# LED_Array.net
KiCad netlist of a schematic drawn in Altium Designer
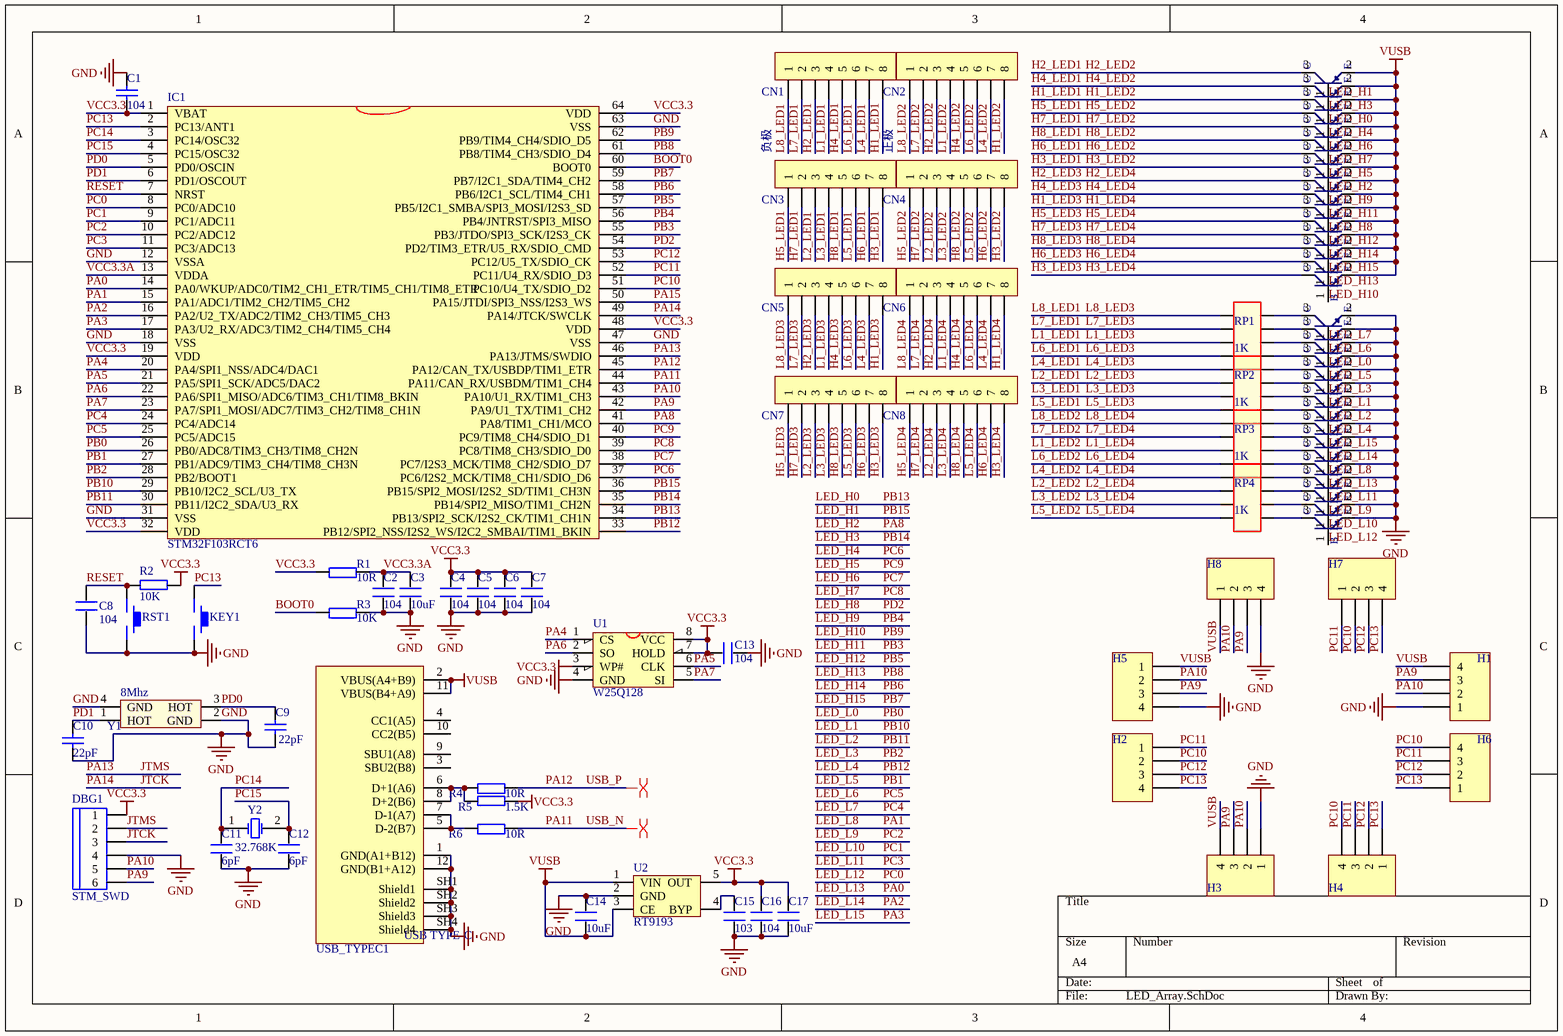
[diagram p0: LED_Array.SchDoc]

(export (version "E")
  (design (tool "Eeschema 10.0.6"))
  (components
    (comp (ref "C1") (value "104") (footprint "C 0603_L") (libsource (lib "L476") (part "CAP")))
    (comp (ref "C2")
      (value "104")
      (footprint "C 0603_L")
      (libsource (lib "WarShip V3 STM32103封装库") (part "C"))
    )
    (comp (ref "C3")
      (value "10uF")
      (footprint "C 0603_L")
      (libsource (lib "WarShip V3 STM32103封装库") (part "C"))
    )
    (comp (ref "C4")
      (value "104")
      (footprint "C 0603_L")
      (libsource (lib "WarShip V3 STM32103封装库") (part "C"))
    )
    (comp (ref "C5")
      (value "104")
      (footprint "C 0603_L")
      (libsource (lib "WarShip V3 STM32103封装库") (part "C"))
    )
    (comp (ref "C6")
      (value "104")
      (footprint "C 0603_L")
      (libsource (lib "WarShip V3 STM32103封装库") (part "C"))
    )
    (comp (ref "C7")
      (value "104")
      (footprint "C 0603_L")
      (libsource (lib "WarShip V3 STM32103封装库") (part "C"))
    )
    (comp (ref "C8")
      (value "104")
      (footprint "C 0603_L")
      (libsource (lib "WarShip V3 STM32103封装库") (part "C"))
    )
    (comp (ref "C9") (value "22pF") (footprint "C 0603_L") (libsource (lib "L476") (part "CAP")))
    (comp (ref "C10") (value "22pF") (footprint "C 0603_L") (libsource (lib "L476") (part "CAP")))
    (comp (ref "C11")
      (value "6pF")
      (footprint "C 0603_L")
      (libsource (lib "WarShip V3 STM32103封装库") (part "C"))
    )
    (comp (ref "C12")
      (value "6pF")
      (footprint "C 0603_L")
      (libsource (lib "WarShip V3 STM32103封装库") (part "C"))
    )
    (comp (ref "C13")
      (value "104")
      (footprint "C 0603_L")
      (libsource (lib "WarShip V3 STM32103封装库") (part "C"))
    )
    (comp (ref "C14")
      (value "10uF")
      (footprint "C 0603_L")
      (libsource (lib "WarShip V3 STM32103封装库") (part "C"))
    )
    (comp (ref "C15")
      (value "103")
      (footprint "C 0603_L")
      (libsource (lib "WarShip V3 STM32103封装库") (part "C"))
    )
    (comp (ref "C16")
      (value "104")
      (footprint "C 0603_L")
      (libsource (lib "WarShip V3 STM32103封装库") (part "C"))
    )
    (comp (ref "C17")
      (value "10uF")
      (footprint "C 0603_L")
      (libsource (lib "WarShip V3 STM32103封装库") (part "C"))
    )
    (comp (ref "CN1")
      (value "HDR-1X8")
      (footprint "HDR2.54-Y-LI-8P")
      (description "8P接插件")
      (libsource (lib "LovelessingSch") (part "Header 8"))
    )
    (comp (ref "CN2")
      (value "HDR-1X8")
      (footprint "HDR2.54-Y-LI-8P")
      (description "8P接插件")
      (libsource (lib "LovelessingSch") (part "Header 8"))
    )
    (comp (ref "CN3")
      (value "HDR-1X8")
      (footprint "HDR2.54-Y-LI-8P")
      (description "8P接插件")
      (libsource (lib "LovelessingSch") (part "Header 8"))
    )
    (comp (ref "CN4")
      (value "HDR-1X8")
      (footprint "HDR2.54-Y-LI-8P")
      (description "8P接插件")
      (libsource (lib "LovelessingSch") (part "Header 8"))
    )
    (comp (ref "CN5")
      (value "HDR-1X8")
      (footprint "HDR2.54-Y-LI-8P")
      (description "8P接插件")
      (libsource (lib "LovelessingSch") (part "Header 8"))
    )
    (comp (ref "CN6")
      (value "HDR-1X8")
      (footprint "HDR2.54-Y-LI-8P")
      (description "8P接插件")
      (libsource (lib "LovelessingSch") (part "Header 8"))
    )
    (comp (ref "CN7")
      (value "HDR-1X8")
      (footprint "HDR2.54-Y-LI-8P")
      (description "8P接插件")
      (libsource (lib "LovelessingSch") (part "Header 8"))
    )
    (comp (ref "CN8")
      (value "HDR-1X8")
      (footprint "HDR2.54-Y-LI-8P")
      (description "8P接插件")
      (libsource (lib "LovelessingSch") (part "Header 8"))
    )
    (comp (ref "DBG1")
      (value "STM_SWD")
      (footprint "SH1.0 S-W-6P")
      (libsource (lib "MiniFly ") (part "HEAD6"))
    )
    (comp (ref "H1")
      (value "Header 4")
      (footprint "HDR2.54-WI-4P")
      (description "Header, 4-Pin")
      (fields (field (name "PUBLISHER") "Altium Limited"))
      (libsource (lib "") (part "Header 4_1"))
    )
    (comp (ref "H2")
      (value "Header 4")
      (footprint "HDR2.54-WI-4P")
      (description "Header, 4-Pin")
      (fields (field (name "PUBLISHER") "Altium Limited"))
      (libsource (lib "LovelessingSch") (part "Header 4"))
    )
    (comp (ref "H3")
      (value "Header 4")
      (footprint "HDR2.54-WI-4P")
      (description "Header, 4-Pin")
      (fields (field (name "PUBLISHER") "Altium Limited"))
      (libsource (lib "LovelessingSch") (part "Header 4"))
    )
    (comp (ref "H4")
      (value "Header 4")
      (footprint "HDR2.54-WI-4P")
      (description "Header, 4-Pin")
      (fields (field (name "PUBLISHER") "Altium Limited"))
      (libsource (lib "LovelessingSch") (part "Header 4"))
    )
    (comp (ref "H5")
      (value "Header 4")
      (footprint "HDR2.54-WI-4P")
      (description "Header, 4-Pin")
      (fields (field (name "PUBLISHER") "Altium Limited"))
      (libsource (lib "LovelessingSch") (part "Header 4"))
    )
    (comp (ref "H6")
      (value "Header 4")
      (footprint "HDR2.54-WI-4P")
      (description "Header, 4-Pin")
      (fields (field (name "PUBLISHER") "Altium Limited"))
      (libsource (lib "") (part "Header 4_1"))
    )
    (comp (ref "H7")
      (value "Header 4")
      (footprint "HDR2.54-WI-4P")
      (description "Header, 4-Pin")
      (fields (field (name "PUBLISHER") "Altium Limited"))
      (libsource (lib "") (part "Header 4_1"))
    )
    (comp (ref "H8")
      (value "Header 4")
      (footprint "HDR2.54-WI-4P")
      (description "Header, 4-Pin")
      (fields (field (name "PUBLISHER") "Altium Limited"))
      (libsource (lib "") (part "Header 4_1"))
    )
    (comp (ref "IC1")
      (value "STM32F103RCT6")
      (footprint "LQFP64 10X10_L")
      (libsource (lib "MiniSTM32 V3.0封装库") (part "STM32F103RDT6"))
    )
    (comp (ref "KEY1")
      (value "KEY-SMD")
      (footprint "TSW SMD-3*6*2.5")
      (description "KEY,SMD,324225")
      (libsource (lib "Pandora_STM32L4_Board_V2.4") (part "S-KEY-SMD-324225"))
    )
    (comp (ref "Q1")
      (value "8550")
      (footprint "SOT23-3L")
      (libsource (lib "LovelessingSch") (part "8550PNP"))
    )
    (comp (ref "Q2")
      (value "8550")
      (footprint "SOT23-3L")
      (libsource (lib "LovelessingSch") (part "8550PNP"))
    )
    (comp (ref "Q3")
      (value "8550")
      (footprint "SOT23-3L")
      (libsource (lib "LovelessingSch") (part "8550PNP"))
    )
    (comp (ref "Q4")
      (value "8550")
      (footprint "SOT23-3L")
      (libsource (lib "LovelessingSch") (part "8550PNP"))
    )
    (comp (ref "Q5")
      (value "8550")
      (footprint "SOT23-3L")
      (libsource (lib "LovelessingSch") (part "8550PNP"))
    )
    (comp (ref "Q6")
      (value "8550")
      (footprint "SOT23-3L")
      (libsource (lib "LovelessingSch") (part "8550PNP"))
    )
    (comp (ref "Q7")
      (value "8550")
      (footprint "SOT23-3L")
      (libsource (lib "LovelessingSch") (part "8550PNP"))
    )
    (comp (ref "Q8")
      (value "8550")
      (footprint "SOT23-3L")
      (libsource (lib "LovelessingSch") (part "8550PNP"))
    )
    (comp (ref "Q9")
      (value "8550")
      (footprint "SOT23-3L")
      (libsource (lib "LovelessingSch") (part "8550PNP"))
    )
    (comp (ref "Q10")
      (value "8550")
      (footprint "SOT23-3L")
      (libsource (lib "LovelessingSch") (part "8550PNP"))
    )
    (comp (ref "Q11")
      (value "8550")
      (footprint "SOT23-3L")
      (libsource (lib "LovelessingSch") (part "8550PNP"))
    )
    (comp (ref "Q12")
      (value "8550")
      (footprint "SOT23-3L")
      (libsource (lib "LovelessingSch") (part "8550PNP"))
    )
    (comp (ref "Q13")
      (value "8550")
      (footprint "SOT23-3L")
      (libsource (lib "LovelessingSch") (part "8550PNP"))
    )
    (comp (ref "Q14")
      (value "8550")
      (footprint "SOT23-3L")
      (libsource (lib "LovelessingSch") (part "8550PNP"))
    )
    (comp (ref "Q15")
      (value "8550")
      (footprint "SOT23-3L")
      (libsource (lib "LovelessingSch") (part "8550PNP"))
    )
    (comp (ref "Q16")
      (value "8550")
      (footprint "SOT23-3L")
      (libsource (lib "LovelessingSch") (part "8550PNP"))
    )
    (comp (ref "Q17")
      (value "8050")
      (footprint "SOT23-3L")
      (libsource (lib "LovelessingSch") (part "8050NPN"))
    )
    (comp (ref "Q18")
      (value "8050")
      (footprint "SOT23-3L")
      (libsource (lib "LovelessingSch") (part "8050NPN"))
    )
    (comp (ref "Q19")
      (value "8050")
      (footprint "SOT23-3L")
      (libsource (lib "LovelessingSch") (part "8050NPN"))
    )
    (comp (ref "Q20")
      (value "8050")
      (footprint "SOT23-3L")
      (libsource (lib "LovelessingSch") (part "8050NPN"))
    )
    (comp (ref "Q21")
      (value "8050")
      (footprint "SOT23-3L")
      (libsource (lib "LovelessingSch") (part "8050NPN"))
    )
    (comp (ref "Q22")
      (value "8050")
      (footprint "SOT23-3L")
      (libsource (lib "LovelessingSch") (part "8050NPN"))
    )
    (comp (ref "Q23")
      (value "8050")
      (footprint "SOT23-3L")
      (libsource (lib "LovelessingSch") (part "8050NPN"))
    )
    (comp (ref "Q24")
      (value "8050")
      (footprint "SOT23-3L")
      (libsource (lib "LovelessingSch") (part "8050NPN"))
    )
    (comp (ref "Q25")
      (value "8050")
      (footprint "SOT23-3L")
      (libsource (lib "LovelessingSch") (part "8050NPN"))
    )
    (comp (ref "Q26")
      (value "8050")
      (footprint "SOT23-3L")
      (libsource (lib "LovelessingSch") (part "8050NPN"))
    )
    (comp (ref "Q27")
      (value "8050")
      (footprint "SOT23-3L")
      (libsource (lib "LovelessingSch") (part "8050NPN"))
    )
    (comp (ref "Q28")
      (value "8050")
      (footprint "SOT23-3L")
      (libsource (lib "LovelessingSch") (part "8050NPN"))
    )
    (comp (ref "Q29")
      (value "8050")
      (footprint "SOT23-3L")
      (libsource (lib "LovelessingSch") (part "8050NPN"))
    )
    (comp (ref "Q30")
      (value "8050")
      (footprint "SOT23-3L")
      (libsource (lib "LovelessingSch") (part "8050NPN"))
    )
    (comp (ref "Q31")
      (value "8050")
      (footprint "SOT23-3L")
      (libsource (lib "LovelessingSch") (part "8050NPN"))
    )
    (comp (ref "Q32")
      (value "8050")
      (footprint "SOT23-3L")
      (libsource (lib "LovelessingSch") (part "8050NPN"))
    )
    (comp (ref "R1")
      (value "10R")
      (footprint "R 0603_L")
      (libsource (lib "WarShip V3 STM32103封装库") (part "R"))
    )
    (comp (ref "R2")
      (value "10K")
      (footprint "R 0603_L")
      (libsource (lib "WarShip V3 STM32103封装库") (part "R"))
    )
    (comp (ref "R3")
      (value "10K")
      (footprint "R 0603_L")
      (libsource (lib "WarShip V3 STM32103封装库") (part "R"))
    )
    (comp (ref "R4")
      (value "10R")
      (footprint "R 0603_L")
      (libsource (lib "WarShip V3 STM32103封装库") (part "R"))
    )
    (comp (ref "R5")
      (value "1.5K")
      (footprint "R 0603_L")
      (libsource (lib "WarShip V3 STM32103封装库") (part "R"))
    )
    (comp (ref "R6")
      (value "10R")
      (footprint "R 0603_L")
      (libsource (lib "WarShip V3 STM32103封装库") (part "R"))
    )
    (comp (ref "RP1")
      (value "1K")
      (footprint "P_pack")
      (description "贴片排阻")
      (libsource (lib "LovelessingSch") (part "R_pack"))
    )
    (comp (ref "RP2")
      (value "1K")
      (footprint "P_pack")
      (description "贴片排阻")
      (libsource (lib "LovelessingSch") (part "R_pack"))
    )
    (comp (ref "RP3")
      (value "1K")
      (footprint "P_pack")
      (description "贴片排阻")
      (libsource (lib "LovelessingSch") (part "R_pack"))
    )
    (comp (ref "RP4")
      (value "1K")
      (footprint "P_pack")
      (description "贴片排阻")
      (libsource (lib "LovelessingSch") (part "R_pack"))
    )
    (comp (ref "RST1")
      (value "KEY-SMD")
      (footprint "TSW SMD-3*6*2.5")
      (description "KEY,SMD,324225")
      (libsource (lib "Pandora_STM32L4_Board_V2.4") (part "S-KEY-SMD-324225"))
    )
    (comp (ref "U1")
      (value "W25Q128")
      (footprint "SOP8W_L")
      (description "W25X16;SST25VF016;MX25L1605")
      (libsource (lib "WarShip V3 STM32103封装库") (part "W25X16"))
    )
    (comp (ref "U2")
      (value "RT9193")
      (footprint "SOT23-5L")
      (description "3.3V 500mA LDO")
      (libsource (lib "STM32H743核心板封装库") (part "CAT6219-330TD"))
    )
    (comp (ref "USB_TYPEC1")
      (value "USB TypeC")
      (footprint "USB Type-C")
      (description "12P TypeC 母座")
      (libsource (lib "ESP32_Weather") (part "USB Type-C"))
    )
    (comp (ref "Y1")
      (value "8Mhz")
      (footprint "XTAL-3225-4P")
      (description "3225贴片无源晶振")
      (libsource (lib "ALIENTEK_COMPONENT") (part "XTAL_3225"))
    )
    (comp (ref "Y2")
      (value "32.768K")
      (footprint "OSC 3215-2P")
      (description "Crystal Oscillator")
      (fields (field (name "PUBLISHER") "Altium Limited"))
      (libsource (lib "WarShip V3 STM32103封装库") (part "XTAL"))
    )
  )
  (nets
    (net (code "1") (name "/BOOT0") (class "Default")
      (node (ref "IC1") (pin "60") (pinfunction "BOOT0_60") (pintype "passive"))
      (node (ref "R3") (pin "1") (pintype "passive"))
    )
    (net (code "2") (name "/H1_LED1") (class "Default")
      (node (ref "CN1") (pin "8") (pinfunction "8_8") (pintype "passive"))
      (node (ref "CN2") (pin "8") (pinfunction "8_8") (pintype "passive"))
      (node (ref "Q3") (pin "3") (pinfunction "C_3") (pintype "passive"))
    )
    (net (code "3") (name "/H1_LED3") (class "Default")
      (node (ref "CN5") (pin "8") (pinfunction "8_8") (pintype "passive"))
      (node (ref "CN6") (pin "8") (pinfunction "8_8") (pintype "passive"))
      (node (ref "Q11") (pin "3") (pinfunction "C_3") (pintype "passive"))
    )
    (net (code "4") (name "/H2_LED1") (class "Default")
      (node (ref "CN1") (pin "3") (pinfunction "3_3") (pintype "passive"))
      (node (ref "CN2") (pin "3") (pinfunction "3_3") (pintype "passive"))
      (node (ref "Q1") (pin "3") (pinfunction "C_3") (pintype "passive"))
    )
    (net (code "5") (name "/H2_LED3") (class "Default")
      (node (ref "CN5") (pin "3") (pinfunction "3_3") (pintype "passive"))
      (node (ref "CN6") (pin "3") (pinfunction "3_3") (pintype "passive"))
      (node (ref "Q9") (pin "3") (pinfunction "C_3") (pintype "passive"))
    )
    (net (code "6") (name "/H3_LED1") (class "Default")
      (node (ref "CN3") (pin "8") (pinfunction "8_8") (pintype "passive"))
      (node (ref "CN4") (pin "8") (pinfunction "8_8") (pintype "passive"))
      (node (ref "Q8") (pin "3") (pinfunction "C_3") (pintype "passive"))
    )
    (net (code "7") (name "/H3_LED3") (class "Default")
      (node (ref "CN7") (pin "8") (pinfunction "8_8") (pintype "passive"))
      (node (ref "CN8") (pin "8") (pinfunction "8_8") (pintype "passive"))
      (node (ref "Q16") (pin "3") (pinfunction "C_3") (pintype "passive"))
    )
    (net (code "8") (name "/H4_LED1") (class "Default")
      (node (ref "CN1") (pin "5") (pinfunction "5_5") (pintype "passive"))
      (node (ref "CN2") (pin "5") (pinfunction "5_5") (pintype "passive"))
      (node (ref "Q2") (pin "3") (pinfunction "C_3") (pintype "passive"))
    )
    (net (code "9") (name "/H4_LED3") (class "Default")
      (node (ref "CN5") (pin "5") (pinfunction "5_5") (pintype "passive"))
      (node (ref "CN6") (pin "5") (pinfunction "5_5") (pintype "passive"))
      (node (ref "Q10") (pin "3") (pinfunction "C_3") (pintype "passive"))
    )
    (net (code "10") (name "/H5_LED1") (class "Default")
      (node (ref "CN3") (pin "1") (pinfunction "1_1") (pintype "passive"))
      (node (ref "CN4") (pin "1") (pinfunction "1_1") (pintype "passive"))
      (node (ref "Q4") (pin "3") (pinfunction "C_3") (pintype "passive"))
    )
    (net (code "11") (name "/H5_LED3") (class "Default")
      (node (ref "CN7") (pin "1") (pinfunction "1_1") (pintype "passive"))
      (node (ref "CN8") (pin "1") (pinfunction "1_1") (pintype "passive"))
      (node (ref "Q12") (pin "3") (pinfunction "C_3") (pintype "passive"))
    )
    (net (code "12") (name "/H6_LED1") (class "Default")
      (node (ref "CN3") (pin "7") (pinfunction "7_7") (pintype "passive"))
      (node (ref "CN4") (pin "7") (pinfunction "7_7") (pintype "passive"))
      (node (ref "Q7") (pin "3") (pinfunction "C_3") (pintype "passive"))
    )
    (net (code "13") (name "/H6_LED3") (class "Default")
      (node (ref "CN7") (pin "7") (pinfunction "7_7") (pintype "passive"))
      (node (ref "CN8") (pin "7") (pinfunction "7_7") (pintype "passive"))
      (node (ref "Q15") (pin "3") (pinfunction "C_3") (pintype "passive"))
    )
    (net (code "14") (name "/H7_LED1") (class "Default")
      (node (ref "CN3") (pin "2") (pinfunction "2_2") (pintype "passive"))
      (node (ref "CN4") (pin "2") (pinfunction "2_2") (pintype "passive"))
      (node (ref "Q5") (pin "3") (pinfunction "C_3") (pintype "passive"))
    )
    (net (code "15") (name "/H7_LED3") (class "Default")
      (node (ref "CN7") (pin "2") (pinfunction "2_2") (pintype "passive"))
      (node (ref "CN8") (pin "2") (pinfunction "2_2") (pintype "passive"))
      (node (ref "Q13") (pin "3") (pinfunction "C_3") (pintype "passive"))
    )
    (net (code "16") (name "/H8_LED1") (class "Default")
      (node (ref "CN3") (pin "5") (pinfunction "5_5") (pintype "passive"))
      (node (ref "CN4") (pin "5") (pinfunction "5_5") (pintype "passive"))
      (node (ref "Q6") (pin "3") (pinfunction "C_3") (pintype "passive"))
    )
    (net (code "17") (name "/H8_LED3") (class "Default")
      (node (ref "CN7") (pin "5") (pinfunction "5_5") (pintype "passive"))
      (node (ref "CN8") (pin "5") (pinfunction "5_5") (pintype "passive"))
      (node (ref "Q14") (pin "3") (pinfunction "C_3") (pintype "passive"))
    )
    (net (code "18") (name "/JTCK") (class "Default")
      (node (ref "DBG1") (pin "3") (pinfunction "3_3") (pintype "passive"))
      (node (ref "IC1") (pin "49") (pinfunction "PA14/JTCK/SWCLK_49") (pintype "passive"))
    )
    (net (code "19") (name "/JTMS") (class "Default")
      (node (ref "DBG1") (pin "2") (pinfunction "2_2") (pintype "passive"))
      (node (ref "IC1") (pin "46") (pinfunction "PA13/JTMS/SWDIO_46") (pintype "passive"))
    )
    (net (code "20") (name "/L1_LED1") (class "Default")
      (node (ref "CN1") (pin "4") (pinfunction "4_4") (pintype "passive"))
      (node (ref "CN5") (pin "4") (pinfunction "4_4") (pintype "passive"))
      (node (ref "RP1") (pin "5") (pintype "passive"))
    )
    (net (code "21") (name "/L1_LED2") (class "Default")
      (node (ref "CN2") (pin "4") (pinfunction "4_4") (pintype "passive"))
      (node (ref "CN6") (pin "4") (pinfunction "4_4") (pintype "passive"))
      (node (ref "RP3") (pin "5") (pintype "passive"))
    )
    (net (code "22") (name "/L2_LED1") (class "Default")
      (node (ref "CN3") (pin "3") (pinfunction "3_3") (pintype "passive"))
      (node (ref "CN7") (pin "3") (pinfunction "3_3") (pintype "passive"))
      (node (ref "RP2") (pin "3") (pintype "passive"))
    )
    (net (code "23") (name "/L2_LED2") (class "Default")
      (node (ref "CN4") (pin "3") (pinfunction "3_3") (pintype "passive"))
      (node (ref "CN8") (pin "3") (pinfunction "3_3") (pintype "passive"))
      (node (ref "RP4") (pin "3") (pintype "passive"))
    )
    (net (code "24") (name "/L3_LED1") (class "Default")
      (node (ref "CN3") (pin "4") (pinfunction "4_4") (pintype "passive"))
      (node (ref "CN7") (pin "4") (pinfunction "4_4") (pintype "passive"))
      (node (ref "RP2") (pin "5") (pintype "passive"))
    )
    (net (code "25") (name "/L3_LED2") (class "Default")
      (node (ref "CN4") (pin "4") (pinfunction "4_4") (pintype "passive"))
      (node (ref "CN8") (pin "4") (pinfunction "4_4") (pintype "passive"))
      (node (ref "RP4") (pin "5") (pintype "passive"))
    )
    (net (code "26") (name "/L4_LED1") (class "Default")
      (node (ref "CN1") (pin "7") (pinfunction "7_7") (pintype "passive"))
      (node (ref "CN5") (pin "7") (pinfunction "7_7") (pintype "passive"))
      (node (ref "RP2") (pin "1") (pinfunction "1_1") (pintype "passive"))
    )
    (net (code "27") (name "/L4_LED2") (class "Default")
      (node (ref "CN2") (pin "7") (pinfunction "7_7") (pintype "passive"))
      (node (ref "CN6") (pin "7") (pinfunction "7_7") (pintype "passive"))
      (node (ref "RP4") (pin "1") (pinfunction "1_1") (pintype "passive"))
    )
    (net (code "28") (name "/L5_LED1") (class "Default")
      (node (ref "CN3") (pin "6") (pinfunction "6_6") (pintype "passive"))
      (node (ref "CN7") (pin "6") (pinfunction "6_6") (pintype "passive"))
      (node (ref "RP2") (pin "7") (pintype "passive"))
    )
    (net (code "29") (name "/L5_LED2") (class "Default")
      (node (ref "CN4") (pin "6") (pinfunction "6_6") (pintype "passive"))
      (node (ref "CN8") (pin "6") (pinfunction "6_6") (pintype "passive"))
      (node (ref "RP4") (pin "7") (pintype "passive"))
    )
    (net (code "30") (name "/L6_LED1") (class "Default")
      (node (ref "CN1") (pin "6") (pinfunction "6_6") (pintype "passive"))
      (node (ref "CN5") (pin "6") (pinfunction "6_6") (pintype "passive"))
      (node (ref "RP1") (pin "7") (pintype "passive"))
    )
    (net (code "31") (name "/L6_LED2") (class "Default")
      (node (ref "CN2") (pin "6") (pinfunction "6_6") (pintype "passive"))
      (node (ref "CN6") (pin "6") (pinfunction "6_6") (pintype "passive"))
      (node (ref "RP3") (pin "7") (pintype "passive"))
    )
    (net (code "32") (name "/L7_LED1") (class "Default")
      (node (ref "CN1") (pin "2") (pinfunction "2_2") (pintype "passive"))
      (node (ref "CN5") (pin "2") (pinfunction "2_2") (pintype "passive"))
      (node (ref "RP1") (pin "3") (pintype "passive"))
    )
    (net (code "33") (name "/L7_LED2") (class "Default")
      (node (ref "CN2") (pin "2") (pinfunction "2_2") (pintype "passive"))
      (node (ref "CN6") (pin "2") (pinfunction "2_2") (pintype "passive"))
      (node (ref "RP3") (pin "3") (pintype "passive"))
    )
    (net (code "34") (name "/L8_LED1") (class "Default")
      (node (ref "CN1") (pin "1") (pinfunction "1_1") (pintype "passive"))
      (node (ref "CN5") (pin "1") (pinfunction "1_1") (pintype "passive"))
      (node (ref "RP1") (pin "1") (pinfunction "1_1") (pintype "passive"))
    )
    (net (code "35") (name "/L8_LED2") (class "Default")
      (node (ref "CN2") (pin "1") (pinfunction "1_1") (pintype "passive"))
      (node (ref "CN6") (pin "1") (pinfunction "1_1") (pintype "passive"))
      (node (ref "RP3") (pin "1") (pinfunction "1_1") (pintype "passive"))
    )
    (net (code "36") (name "/LED_H0") (class "Default")
      (node (ref "IC1") (pin "34") (pinfunction "PB13/SPI2_SCK/I2S2_CK/TIM1_CH1N_34") (pintype "passive"))
      (node (ref "Q3") (pin "1") (pinfunction "B_1") (pintype "passive"))
    )
    (net (code "37") (name "/LED_H1") (class "Default")
      (node (ref "IC1") (pin "36") (pinfunction "PB15/SPI2_MOSI/I2S2_SD/TIM1_CH3N_36") (pintype "passive"))
      (node (ref "Q1") (pin "1") (pinfunction "B_1") (pintype "passive"))
    )
    (net (code "38") (name "/LED_H2") (class "Default")
      (node (ref "IC1") (pin "41") (pinfunction "PA8/TIM1_CH1/MCO_41") (pintype "passive"))
      (node (ref "Q8") (pin "1") (pinfunction "B_1") (pintype "passive"))
    )
    (net (code "39") (name "/LED_H3") (class "Default")
      (node (ref "IC1") (pin "35") (pinfunction "PB14/SPI2_MISO/TIM1_CH2N_35") (pintype "passive"))
      (node (ref "Q2") (pin "1") (pinfunction "B_1") (pintype "passive"))
    )
    (net (code "40") (name "/LED_H4") (class "Default")
      (node (ref "IC1") (pin "37") (pinfunction "PC6/I2S2_MCK/TIM8_CH1/SDIO_D6_37") (pintype "passive"))
      (node (ref "Q4") (pin "1") (pinfunction "B_1") (pintype "passive"))
    )
    (net (code "41") (name "/LED_H5") (class "Default")
      (node (ref "IC1") (pin "40") (pinfunction "PC9/TIM8_CH4/SDIO_D1_40") (pintype "passive"))
      (node (ref "Q7") (pin "1") (pinfunction "B_1") (pintype "passive"))
    )
    (net (code "42") (name "/LED_H6") (class "Default")
      (node (ref "IC1") (pin "38") (pinfunction "PC7/I2S3_MCK/TIM8_CH2/SDIO_D7_38") (pintype "passive"))
      (node (ref "Q5") (pin "1") (pinfunction "B_1") (pintype "passive"))
    )
    (net (code "43") (name "/LED_H7") (class "Default")
      (node (ref "IC1") (pin "39") (pinfunction "PC8/TIM8_CH3/SDIO_D0_39") (pintype "passive"))
      (node (ref "Q6") (pin "1") (pinfunction "B_1") (pintype "passive"))
    )
    (net (code "44") (name "/LED_H8") (class "Default")
      (node (ref "IC1") (pin "54") (pinfunction "PD2/TIM3_ETR/U5_RX/SDIO_CMD_54") (pintype "passive"))
      (node (ref "Q11") (pin "1") (pinfunction "B_1") (pintype "passive"))
    )
    (net (code "45") (name "/LED_H9") (class "Default")
      (node (ref "IC1") (pin "56") (pinfunction "PB4/JNTRST/SPI3_MISO_56") (pintype "passive"))
      (node (ref "Q9") (pin "1") (pinfunction "B_1") (pintype "passive"))
    )
    (net (code "46") (name "/LED_H10") (class "Default")
      (node (ref "IC1") (pin "62") (pinfunction "PB9/TIM4_CH4/SDIO_D5_62") (pintype "passive"))
      (node (ref "Q16") (pin "1") (pinfunction "B_1") (pintype "passive"))
    )
    (net (code "47") (name "/LED_H11") (class "Default")
      (node (ref "IC1") (pin "55") (pinfunction "PB3/JTDO/SPI3_SCK/I2S3_CK_55") (pintype "passive"))
      (node (ref "Q10") (pin "1") (pinfunction "B_1") (pintype "passive"))
    )
    (net (code "48") (name "/LED_H12") (class "Default")
      (node (ref "IC1") (pin "57") (pinfunction "PB5/I2C1_SMBA/SPI3_MOSI/I2S3_SD_57") (pintype "passive"))
      (node (ref "Q12") (pin "1") (pinfunction "B_1") (pintype "passive"))
    )
    (net (code "49") (name "/LED_H13") (class "Default")
      (node (ref "IC1") (pin "61") (pinfunction "PB8/TIM4_CH3/SDIO_D4_61") (pintype "passive"))
      (node (ref "Q15") (pin "1") (pinfunction "B_1") (pintype "passive"))
    )
    (net (code "50") (name "/LED_H14") (class "Default")
      (node (ref "IC1") (pin "58") (pinfunction "PB6/I2C1_SCL/TIM4_CH1_58") (pintype "passive"))
      (node (ref "Q13") (pin "1") (pinfunction "B_1") (pintype "passive"))
    )
    (net (code "51") (name "/LED_H15") (class "Default")
      (node (ref "IC1") (pin "59") (pinfunction "PB7/I2C1_SDA/TIM4_CH2_59") (pintype "passive"))
      (node (ref "Q14") (pin "1") (pinfunction "B_1") (pintype "passive"))
    )
    (net (code "52") (name "/LED_L0") (class "Default")
      (node (ref "IC1") (pin "26") (pinfunction "PB0/ADC8/TIM3_CH3/TIM8_CH2N_26") (pintype "passive"))
      (node (ref "Q19") (pin "1") (pinfunction "B_1") (pintype "passive"))
    )
    (net (code "53") (name "/LED_L1") (class "Default")
      (node (ref "IC1") (pin "29") (pinfunction "PB10/I2C2_SCL/U3_TX_29") (pintype "passive"))
      (node (ref "Q22") (pin "1") (pinfunction "B_1") (pintype "passive"))
    )
    (net (code "54") (name "/LED_L2") (class "Default")
      (node (ref "IC1") (pin "30") (pinfunction "PB11/I2C2_SDA/U3_RX_30") (pintype "passive"))
      (node (ref "Q23") (pin "1") (pinfunction "B_1") (pintype "passive"))
    )
    (net (code "55") (name "/LED_L3") (class "Default")
      (node (ref "IC1") (pin "28") (pinfunction "PB2/BOOT1_28") (pintype "passive"))
      (node (ref "Q21") (pin "1") (pinfunction "B_1") (pintype "passive"))
    )
    (net (code "56") (name "/LED_L4") (class "Default")
      (node (ref "IC1") (pin "33") (pinfunction "PB12/SPI2_NSS/I2S2_WS/I2C2_SMBAI/TIM1_BKIN_33") (pintype "passive"))
      (node (ref "Q24") (pin "1") (pinfunction "B_1") (pintype "passive"))
    )
    (net (code "57") (name "/LED_L5") (class "Default")
      (node (ref "IC1") (pin "27") (pinfunction "PB1/ADC9/TIM3_CH4/TIM8_CH3N_27") (pintype "passive"))
      (node (ref "Q20") (pin "1") (pinfunction "B_1") (pintype "passive"))
    )
    (net (code "58") (name "/LED_L6") (class "Default")
      (node (ref "IC1") (pin "25") (pinfunction "PC5/ADC15_25") (pintype "passive"))
      (node (ref "Q18") (pin "1") (pinfunction "B_1") (pintype "passive"))
    )
    (net (code "59") (name "/LED_L7") (class "Default")
      (node (ref "IC1") (pin "24") (pinfunction "PC4/ADC14_24") (pintype "passive"))
      (node (ref "Q17") (pin "1") (pinfunction "B_1") (pintype "passive"))
    )
    (net (code "60") (name "/LED_L8") (class "Default")
      (node (ref "IC1") (pin "15") (pinfunction "PA1/ADC1/TIM2_CH2/TIM5_CH2_15") (pintype "passive"))
      (node (ref "Q27") (pin "1") (pinfunction "B_1") (pintype "passive"))
    )
    (net (code "61") (name "/LED_L9") (class "Default")
      (node (ref "IC1") (pin "10") (pinfunction "PC2/ADC12_10") (pintype "passive"))
      (node (ref "Q30") (pin "1") (pinfunction "B_1") (pintype "passive"))
    )
    (net (code "62") (name "/LED_L10") (class "Default")
      (node (ref "IC1") (pin "9") (pinfunction "PC1/ADC11_9") (pintype "passive"))
      (node (ref "Q31") (pin "1") (pinfunction "B_1") (pintype "passive"))
    )
    (net (code "63") (name "/LED_L11") (class "Default")
      (node (ref "IC1") (pin "11") (pinfunction "PC3/ADC13_11") (pintype "passive"))
      (node (ref "Q29") (pin "1") (pinfunction "B_1") (pintype "passive"))
    )
    (net (code "64") (name "/LED_L12") (class "Default")
      (node (ref "IC1") (pin "8") (pinfunction "PC0/ADC10_8") (pintype "passive"))
      (node (ref "Q32") (pin "1") (pinfunction "B_1") (pintype "passive"))
    )
    (net (code "65") (name "/LED_L13") (class "Default")
      (node (ref "IC1") (pin "14") (pinfunction "PA0/WKUP/ADC0/TIM2_CH1_ETR/TIM5_CH1/TIM8_ETR_14") (pintype "passive"))
      (node (ref "Q28") (pin "1") (pinfunction "B_1") (pintype "passive"))
    )
    (net (code "66") (name "/LED_L14") (class "Default")
      (node (ref "IC1") (pin "16") (pinfunction "PA2/U2_TX/ADC2/TIM2_CH3/TIM5_CH3_16") (pintype "passive"))
      (node (ref "Q26") (pin "1") (pinfunction "B_1") (pintype "passive"))
    )
    (net (code "67") (name "/LED_L15") (class "Default")
      (node (ref "IC1") (pin "17") (pinfunction "PA3/U2_RX/ADC3/TIM2_CH4/TIM5_CH4_17") (pintype "passive"))
      (node (ref "Q25") (pin "1") (pinfunction "B_1") (pintype "passive"))
    )
    (net (code "68") (name "/PA4") (class "Default")
      (node (ref "IC1") (pin "20") (pinfunction "PA4/SPI1_NSS/ADC4/DAC1_20") (pintype "passive"))
      (node (ref "U1") (pin "1") (pinfunction "CS_1") (pintype "passive"))
    )
    (net (code "69") (name "/PA5") (class "Default")
      (node (ref "IC1") (pin "21") (pinfunction "PA5/SPI1_SCK/ADC5/DAC2_21") (pintype "passive"))
      (node (ref "U1") (pin "6") (pinfunction "CLK_6") (pintype "passive"))
    )
    (net (code "70") (name "/PA6") (class "Default")
      (node (ref "IC1") (pin "22") (pinfunction "PA6/SPI1_MISO/ADC6/TIM3_CH1/TIM8_BKIN_22") (pintype "passive"))
      (node (ref "U1") (pin "2") (pinfunction "SO_2") (pintype "passive"))
    )
    (net (code "71") (name "/PA7") (class "Default")
      (node (ref "IC1") (pin "23") (pinfunction "PA7/SPI1_MOSI/ADC7/TIM3_CH2/TIM8_CH1N_23") (pintype "passive"))
      (node (ref "U1") (pin "5") (pinfunction "SI_5") (pintype "passive"))
    )
    (net (code "72") (name "/PA9") (class "Default")
      (node (ref "DBG1") (pin "6") (pinfunction "6_6") (pintype "passive"))
      (node (ref "H1") (pin "3") (pinfunction "3_3") (pintype "passive"))
      (node (ref "H3") (pin "3") (pinfunction "3_3") (pintype "passive"))
      (node (ref "H5") (pin "3") (pinfunction "3_3") (pintype "passive"))
      (node (ref "H8") (pin "3") (pinfunction "3_3") (pintype "passive"))
      (node (ref "IC1") (pin "42") (pinfunction "PA9/U1_TX/TIM1_CH2_42") (pintype "passive"))
    )
    (net (code "73") (name "/PA10") (class "Default")
      (node (ref "DBG1") (pin "5") (pinfunction "5_5") (pintype "passive"))
      (node (ref "H1") (pin "2") (pinfunction "2_2") (pintype "passive"))
      (node (ref "H3") (pin "2") (pinfunction "2_2") (pintype "passive"))
      (node (ref "H5") (pin "2") (pinfunction "2_2") (pintype "passive"))
      (node (ref "H8") (pin "2") (pinfunction "2_2") (pintype "passive"))
      (node (ref "IC1") (pin "43") (pinfunction "PA10/U1_RX/TIM1_CH3_43") (pintype "passive"))
    )
    (net (code "74") (name "/PA11") (class "Default")
      (node (ref "IC1") (pin "44") (pinfunction "PA11/CAN_RX/USBDM/TIM1_CH4_44") (pintype "passive"))
      (node (ref "R6") (pin "2") (pintype "passive"))
    )
    (net (code "75") (name "/PA12") (class "Default")
      (node (ref "IC1") (pin "45") (pinfunction "PA12/CAN_TX/USBDP/TIM1_ETR_45") (pintype "passive"))
      (node (ref "R4") (pin "2") (pintype "passive"))
    )
    (net (code "76") (name "/PA15") (class "Default")
      (node (ref "IC1") (pin "50") (pinfunction "PA15/JTDI/SPI3_NSS/I2S3_WS_50") (pintype "passive"))
    )
    (net (code "77") (name "/PC10") (class "Default")
      (node (ref "H2") (pin "2") (pinfunction "2_2") (pintype "passive"))
      (node (ref "H4") (pin "4") (pinfunction "4_4") (pintype "passive"))
      (node (ref "H6") (pin "4") (pinfunction "4_4") (pintype "passive"))
      (node (ref "H7") (pin "2") (pinfunction "2_2") (pintype "passive"))
      (node (ref "IC1") (pin "51") (pinfunction "PC10/U4_TX/SDIO_D2_51") (pintype "passive"))
    )
    (net (code "78") (name "/PC11") (class "Default")
      (node (ref "H2") (pin "1") (pinfunction "1_1") (pintype "passive"))
      (node (ref "H4") (pin "3") (pinfunction "3_3") (pintype "passive"))
      (node (ref "H6") (pin "3") (pinfunction "3_3") (pintype "passive"))
      (node (ref "H7") (pin "1") (pinfunction "1_1") (pintype "passive"))
      (node (ref "IC1") (pin "52") (pinfunction "PC11/U4_RX/SDIO_D3_52") (pintype "passive"))
    )
    (net (code "79") (name "/PC12") (class "Default")
      (node (ref "H2") (pin "3") (pinfunction "3_3") (pintype "passive"))
      (node (ref "H4") (pin "2") (pinfunction "2_2") (pintype "passive"))
      (node (ref "H6") (pin "2") (pinfunction "2_2") (pintype "passive"))
      (node (ref "H7") (pin "3") (pinfunction "3_3") (pintype "passive"))
      (node (ref "IC1") (pin "53") (pinfunction "PC12/U5_TX/SDIO_CK_53") (pintype "passive"))
    )
    (net (code "80") (name "/PC13") (class "Default")
      (node (ref "H2") (pin "4") (pinfunction "4_4") (pintype "passive"))
      (node (ref "H4") (pin "1") (pinfunction "1_1") (pintype "passive"))
      (node (ref "H6") (pin "1") (pinfunction "1_1") (pintype "passive"))
      (node (ref "H7") (pin "4") (pinfunction "4_4") (pintype "passive"))
      (node (ref "IC1") (pin "2") (pinfunction "PC13/ANT1_2") (pintype "passive"))
      (node (ref "KEY1") (pin "1") (pinfunction "1_1") (pintype "passive"))
    )
    (net (code "81") (name "/PC14") (class "Default")
      (node (ref "C11") (pin "2") (pintype "passive"))
      (node (ref "IC1") (pin "3") (pinfunction "PC14/OSC32_3") (pintype "passive"))
      (node (ref "Y2") (pin "1") (pinfunction "OSC1_1") (pintype "passive"))
    )
    (net (code "82") (name "/PC15") (class "Default")
      (node (ref "C12") (pin "2") (pintype "passive"))
      (node (ref "IC1") (pin "4") (pinfunction "PC15/OSC32_4") (pintype "passive"))
      (node (ref "Y2") (pin "2") (pinfunction "OSC2_2") (pintype "passive"))
    )
    (net (code "83") (name "/PD0") (class "Default")
      (node (ref "C9") (pin "2") (pinfunction "2_2") (pintype "passive"))
      (node (ref "IC1") (pin "5") (pinfunction "PD0/OSCIN_5") (pintype "passive"))
      (node (ref "Y1") (pin "3") (pinfunction "HOT_3") (pintype "passive"))
    )
    (net (code "84") (name "/PD1") (class "Default")
      (node (ref "C10") (pin "2") (pinfunction "2_2") (pintype "passive"))
      (node (ref "IC1") (pin "6") (pinfunction "PD1/OSCOUT_6") (pintype "passive"))
      (node (ref "Y1") (pin "1") (pinfunction "HOT_1") (pintype "passive"))
    )
    (net (code "85") (name "/RESET") (class "Default")
      (node (ref "C8") (pin "2") (pintype "passive"))
      (node (ref "IC1") (pin "7") (pinfunction "NRST_7") (pintype "passive"))
      (node (ref "R2") (pin "2") (pintype "passive"))
      (node (ref "RST1") (pin "1") (pinfunction "1_1") (pintype "passive"))
    )
    (net (code "86") (name "/VCC3.3A") (class "Default")
      (node (ref "C2") (pin "2") (pintype "passive"))
      (node (ref "C3") (pin "2") (pintype "passive"))
      (node (ref "IC1") (pin "13") (pinfunction "VDDA_13") (pintype "passive"))
      (node (ref "R1") (pin "2") (pintype "passive"))
    )
    (net (code "87") (name "GND") (class "Default")
      (node (ref "C1") (pin "1") (pinfunction "1_1") (pintype "passive"))
      (node (ref "C10") (pin "1") (pinfunction "1_1") (pintype "passive"))
      (node (ref "C11") (pin "1") (pintype "passive"))
      (node (ref "C12") (pin "1") (pintype "passive"))
      (node (ref "C13") (pin "2") (pintype "passive"))
      (node (ref "C14") (pin "2") (pintype "passive"))
      (node (ref "C15") (pin "1") (pintype "passive"))
      (node (ref "C16") (pin "1") (pintype "passive"))
      (node (ref "C17") (pin "1") (pintype "passive"))
      (node (ref "C2") (pin "1") (pintype "passive"))
      (node (ref "C3") (pin "1") (pintype "passive"))
      (node (ref "C4") (pin "1") (pintype "passive"))
      (node (ref "C5") (pin "1") (pintype "passive"))
      (node (ref "C6") (pin "1") (pintype "passive"))
      (node (ref "C7") (pin "1") (pintype "passive"))
      (node (ref "C8") (pin "1") (pintype "passive"))
      (node (ref "C9") (pin "1") (pinfunction "1_1") (pintype "passive"))
      (node (ref "DBG1") (pin "4") (pinfunction "4_4") (pintype "passive"))
      (node (ref "H1") (pin "1") (pinfunction "1_1") (pintype "passive"))
      (node (ref "H3") (pin "1") (pinfunction "1_1") (pintype "passive"))
      (node (ref "H5") (pin "4") (pinfunction "4_4") (pintype "passive"))
      (node (ref "H8") (pin "4") (pinfunction "4_4") (pintype "passive"))
      (node (ref "IC1") (pin "12") (pinfunction "VSSA_12") (pintype "passive"))
      (node (ref "IC1") (pin "18") (pinfunction "VSS_18") (pintype "passive"))
      (node (ref "IC1") (pin "31") (pinfunction "VSS_31") (pintype "passive"))
      (node (ref "IC1") (pin "47") (pinfunction "VSS_47") (pintype "passive"))
      (node (ref "IC1") (pin "63") (pinfunction "VSS_63") (pintype "passive"))
      (node (ref "KEY1") (pin "2") (pinfunction "2_2") (pintype "passive"))
      (node (ref "Q17") (pin "2") (pinfunction "E_2") (pintype "passive"))
      (node (ref "Q18") (pin "2") (pinfunction "E_2") (pintype "passive"))
      (node (ref "Q19") (pin "2") (pinfunction "E_2") (pintype "passive"))
      (node (ref "Q20") (pin "2") (pinfunction "E_2") (pintype "passive"))
      (node (ref "Q21") (pin "2") (pinfunction "E_2") (pintype "passive"))
      (node (ref "Q22") (pin "2") (pinfunction "E_2") (pintype "passive"))
      (node (ref "Q23") (pin "2") (pinfunction "E_2") (pintype "passive"))
      (node (ref "Q24") (pin "2") (pinfunction "E_2") (pintype "passive"))
      (node (ref "Q25") (pin "2") (pinfunction "E_2") (pintype "passive"))
      (node (ref "Q26") (pin "2") (pinfunction "E_2") (pintype "passive"))
      (node (ref "Q27") (pin "2") (pinfunction "E_2") (pintype "passive"))
      (node (ref "Q28") (pin "2") (pinfunction "E_2") (pintype "passive"))
      (node (ref "Q29") (pin "2") (pinfunction "E_2") (pintype "passive"))
      (node (ref "Q30") (pin "2") (pinfunction "E_2") (pintype "passive"))
      (node (ref "Q31") (pin "2") (pinfunction "E_2") (pintype "passive"))
      (node (ref "Q32") (pin "2") (pinfunction "E_2") (pintype "passive"))
      (node (ref "R3") (pin "2") (pintype "passive"))
      (node (ref "RST1") (pin "2") (pinfunction "2_2") (pintype "passive"))
      (node (ref "U1") (pin "4") (pinfunction "GND_4") (pintype "passive"))
      (node (ref "U2") (pin "2") (pinfunction "GND_2") (pintype "passive"))
      (node (ref "USB_TYPEC1") (pin "1") (pinfunction "GND(A1+B12)_1") (pintype "passive"))
      (node (ref "USB_TYPEC1") (pin "12") (pinfunction "GND(B1+A12)_12") (pintype "passive"))
      (node (ref "USB_TYPEC1") (pin "SH1") (pinfunction "Shield1_SH1") (pintype "passive"))
      (node (ref "USB_TYPEC1") (pin "SH2") (pinfunction "Shield2_SH2") (pintype "passive"))
      (node (ref "USB_TYPEC1") (pin "SH3") (pinfunction "Shield3_SH3") (pintype "passive"))
      (node (ref "USB_TYPEC1") (pin "SH4") (pinfunction "Shield4_SH4") (pintype "passive"))
      (node (ref "Y1") (pin "2") (pinfunction "GND_2") (pintype "passive"))
      (node (ref "Y1") (pin "4") (pinfunction "GND_4") (pintype "passive"))
    )
    (net (code "88") (name "Net-(Q17-C)") (class "Default")
      (node (ref "Q17") (pin "3") (pinfunction "C_3") (pintype "passive"))
      (node (ref "RP1") (pin "2") (pintype "passive"))
    )
    (net (code "89") (name "Net-(Q18-C)") (class "Default")
      (node (ref "Q18") (pin "3") (pinfunction "C_3") (pintype "passive"))
      (node (ref "RP1") (pin "4") (pintype "passive"))
    )
    (net (code "90") (name "Net-(Q19-C)") (class "Default")
      (node (ref "Q19") (pin "3") (pinfunction "C_3") (pintype "passive"))
      (node (ref "RP1") (pin "6") (pintype "passive"))
    )
    (net (code "91") (name "Net-(Q20-C)") (class "Default")
      (node (ref "Q20") (pin "3") (pinfunction "C_3") (pintype "passive"))
      (node (ref "RP1") (pin "8") (pintype "passive"))
    )
    (net (code "92") (name "Net-(Q21-C)") (class "Default")
      (node (ref "Q21") (pin "3") (pinfunction "C_3") (pintype "passive"))
      (node (ref "RP2") (pin "2") (pintype "passive"))
    )
    (net (code "93") (name "Net-(Q22-C)") (class "Default")
      (node (ref "Q22") (pin "3") (pinfunction "C_3") (pintype "passive"))
      (node (ref "RP2") (pin "4") (pintype "passive"))
    )
    (net (code "94") (name "Net-(Q23-C)") (class "Default")
      (node (ref "Q23") (pin "3") (pinfunction "C_3") (pintype "passive"))
      (node (ref "RP2") (pin "6") (pintype "passive"))
    )
    (net (code "95") (name "Net-(Q24-C)") (class "Default")
      (node (ref "Q24") (pin "3") (pinfunction "C_3") (pintype "passive"))
      (node (ref "RP2") (pin "8") (pintype "passive"))
    )
    (net (code "96") (name "Net-(Q25-C)") (class "Default")
      (node (ref "Q25") (pin "3") (pinfunction "C_3") (pintype "passive"))
      (node (ref "RP3") (pin "2") (pintype "passive"))
    )
    (net (code "97") (name "Net-(Q26-C)") (class "Default")
      (node (ref "Q26") (pin "3") (pinfunction "C_3") (pintype "passive"))
      (node (ref "RP3") (pin "4") (pintype "passive"))
    )
    (net (code "98") (name "Net-(Q27-C)") (class "Default")
      (node (ref "Q27") (pin "3") (pinfunction "C_3") (pintype "passive"))
      (node (ref "RP3") (pin "6") (pintype "passive"))
    )
    (net (code "99") (name "Net-(Q28-C)") (class "Default")
      (node (ref "Q28") (pin "3") (pinfunction "C_3") (pintype "passive"))
      (node (ref "RP3") (pin "8") (pintype "passive"))
    )
    (net (code "100") (name "Net-(Q29-C)") (class "Default")
      (node (ref "Q29") (pin "3") (pinfunction "C_3") (pintype "passive"))
      (node (ref "RP4") (pin "2") (pintype "passive"))
    )
    (net (code "101") (name "Net-(Q30-C)") (class "Default")
      (node (ref "Q30") (pin "3") (pinfunction "C_3") (pintype "passive"))
      (node (ref "RP4") (pin "4") (pintype "passive"))
    )
    (net (code "102") (name "Net-(Q31-C)") (class "Default")
      (node (ref "Q31") (pin "3") (pinfunction "C_3") (pintype "passive"))
      (node (ref "RP4") (pin "6") (pintype "passive"))
    )
    (net (code "103") (name "Net-(Q32-C)") (class "Default")
      (node (ref "Q32") (pin "3") (pinfunction "C_3") (pintype "passive"))
      (node (ref "RP4") (pin "8") (pintype "passive"))
    )
    (net (code "104") (name "Net-(U2-BYP)") (class "Default")
      (node (ref "C15") (pin "2") (pintype "passive"))
      (node (ref "U2") (pin "4") (pinfunction "BYP_4") (pintype "passive"))
    )
    (net (code "105") (name "Net-(USB_TYPEC1-D+1(A6))") (class "Default")
      (node (ref "R4") (pin "1") (pintype "passive"))
      (node (ref "R5") (pin "2") (pintype "passive"))
      (node (ref "USB_TYPEC1") (pin "6") (pinfunction "D+1(A6)_6") (pintype "passive"))
      (node (ref "USB_TYPEC1") (pin "8") (pinfunction "D+2(B6)_8") (pintype "passive"))
    )
    (net (code "106") (name "Net-(USB_TYPEC1-D-1(A7))") (class "Default")
      (node (ref "R6") (pin "1") (pintype "passive"))
      (node (ref "USB_TYPEC1") (pin "5") (pinfunction "D-2(B7)_5") (pintype "passive"))
      (node (ref "USB_TYPEC1") (pin "7") (pinfunction "D-1(A7)_7") (pintype "passive"))
    )
    (net (code "107") (name "VCC3.3") (class "Default")
      (node (ref "C1") (pin "2") (pinfunction "2_2") (pintype "passive"))
      (node (ref "C13") (pin "1") (pintype "passive"))
      (node (ref "C16") (pin "2") (pintype "passive"))
      (node (ref "C17") (pin "2") (pintype "passive"))
      (node (ref "C4") (pin "2") (pintype "passive"))
      (node (ref "C5") (pin "2") (pintype "passive"))
      (node (ref "C6") (pin "2") (pintype "passive"))
      (node (ref "C7") (pin "2") (pintype "passive"))
      (node (ref "DBG1") (pin "1") (pinfunction "1_1") (pintype "passive"))
      (node (ref "IC1") (pin "1") (pinfunction "VBAT_1") (pintype "passive"))
      (node (ref "IC1") (pin "19") (pinfunction "VDD_19") (pintype "passive"))
      (node (ref "IC1") (pin "32") (pinfunction "VDD_32") (pintype "passive"))
      (node (ref "IC1") (pin "48") (pinfunction "VDD_48") (pintype "passive"))
      (node (ref "IC1") (pin "64") (pinfunction "VDD_64") (pintype "passive"))
      (node (ref "R1") (pin "1") (pintype "passive"))
      (node (ref "R2") (pin "1") (pintype "passive"))
      (node (ref "R5") (pin "1") (pintype "passive"))
      (node (ref "U1") (pin "3") (pinfunction "WP#_3") (pintype "passive"))
      (node (ref "U1") (pin "7") (pinfunction "HOLD_7") (pintype "passive"))
      (node (ref "U1") (pin "8") (pinfunction "VCC_8") (pintype "passive"))
      (node (ref "U2") (pin "5") (pinfunction "OUT_5") (pintype "passive"))
    )
    (net (code "108") (name "VUSB") (class "Default")
      (node (ref "C14") (pin "1") (pintype "passive"))
      (node (ref "H1") (pin "4") (pinfunction "4_4") (pintype "passive"))
      (node (ref "H3") (pin "4") (pinfunction "4_4") (pintype "passive"))
      (node (ref "H5") (pin "1") (pinfunction "1_1") (pintype "passive"))
      (node (ref "H8") (pin "1") (pinfunction "1_1") (pintype "passive"))
      (node (ref "Q1") (pin "2") (pinfunction "E_2") (pintype "passive"))
      (node (ref "Q10") (pin "2") (pinfunction "E_2") (pintype "passive"))
      (node (ref "Q11") (pin "2") (pinfunction "E_2") (pintype "passive"))
      (node (ref "Q12") (pin "2") (pinfunction "E_2") (pintype "passive"))
      (node (ref "Q13") (pin "2") (pinfunction "E_2") (pintype "passive"))
      (node (ref "Q14") (pin "2") (pinfunction "E_2") (pintype "passive"))
      (node (ref "Q15") (pin "2") (pinfunction "E_2") (pintype "passive"))
      (node (ref "Q16") (pin "2") (pinfunction "E_2") (pintype "passive"))
      (node (ref "Q2") (pin "2") (pinfunction "E_2") (pintype "passive"))
      (node (ref "Q3") (pin "2") (pinfunction "E_2") (pintype "passive"))
      (node (ref "Q4") (pin "2") (pinfunction "E_2") (pintype "passive"))
      (node (ref "Q5") (pin "2") (pinfunction "E_2") (pintype "passive"))
      (node (ref "Q6") (pin "2") (pinfunction "E_2") (pintype "passive"))
      (node (ref "Q7") (pin "2") (pinfunction "E_2") (pintype "passive"))
      (node (ref "Q8") (pin "2") (pinfunction "E_2") (pintype "passive"))
      (node (ref "Q9") (pin "2") (pinfunction "E_2") (pintype "passive"))
      (node (ref "U2") (pin "1") (pinfunction "VIN_1") (pintype "passive"))
      (node (ref "U2") (pin "3") (pinfunction "CE_3") (pintype "passive"))
      (node (ref "USB_TYPEC1") (pin "11") (pinfunction "VBUS(B4+A9)_11") (pintype "passive"))
      (node (ref "USB_TYPEC1") (pin "2") (pinfunction "VBUS(A4+B9)_2") (pintype "passive"))
    )
    (net (code "109") (name "unconnected-(USB_TYPEC1-CC1(A5)-Pad4)") (class "Default")
      (node (ref "USB_TYPEC1") (pin "4") (pinfunction "CC1(A5)_4") (pintype "passive"))
    )
    (net (code "110") (name "unconnected-(USB_TYPEC1-CC2(B5)-Pad10)") (class "Default")
      (node (ref "USB_TYPEC1") (pin "10") (pinfunction "CC2(B5)_10") (pintype "passive"))
    )
    (net (code "111") (name "unconnected-(USB_TYPEC1-SBU1(A8)-Pad9)") (class "Default")
      (node (ref "USB_TYPEC1") (pin "9") (pinfunction "SBU1(A8)_9") (pintype "passive"))
    )
    (net (code "112") (name "unconnected-(USB_TYPEC1-SBU2(B8)-Pad3)") (class "Default")
      (node (ref "USB_TYPEC1") (pin "3") (pinfunction "SBU2(B8)_3") (pintype "passive"))
    )
  )
)
